# Jawbone_v2.net
KiCad netlist of a schematic drawn in EasyEDA Pro
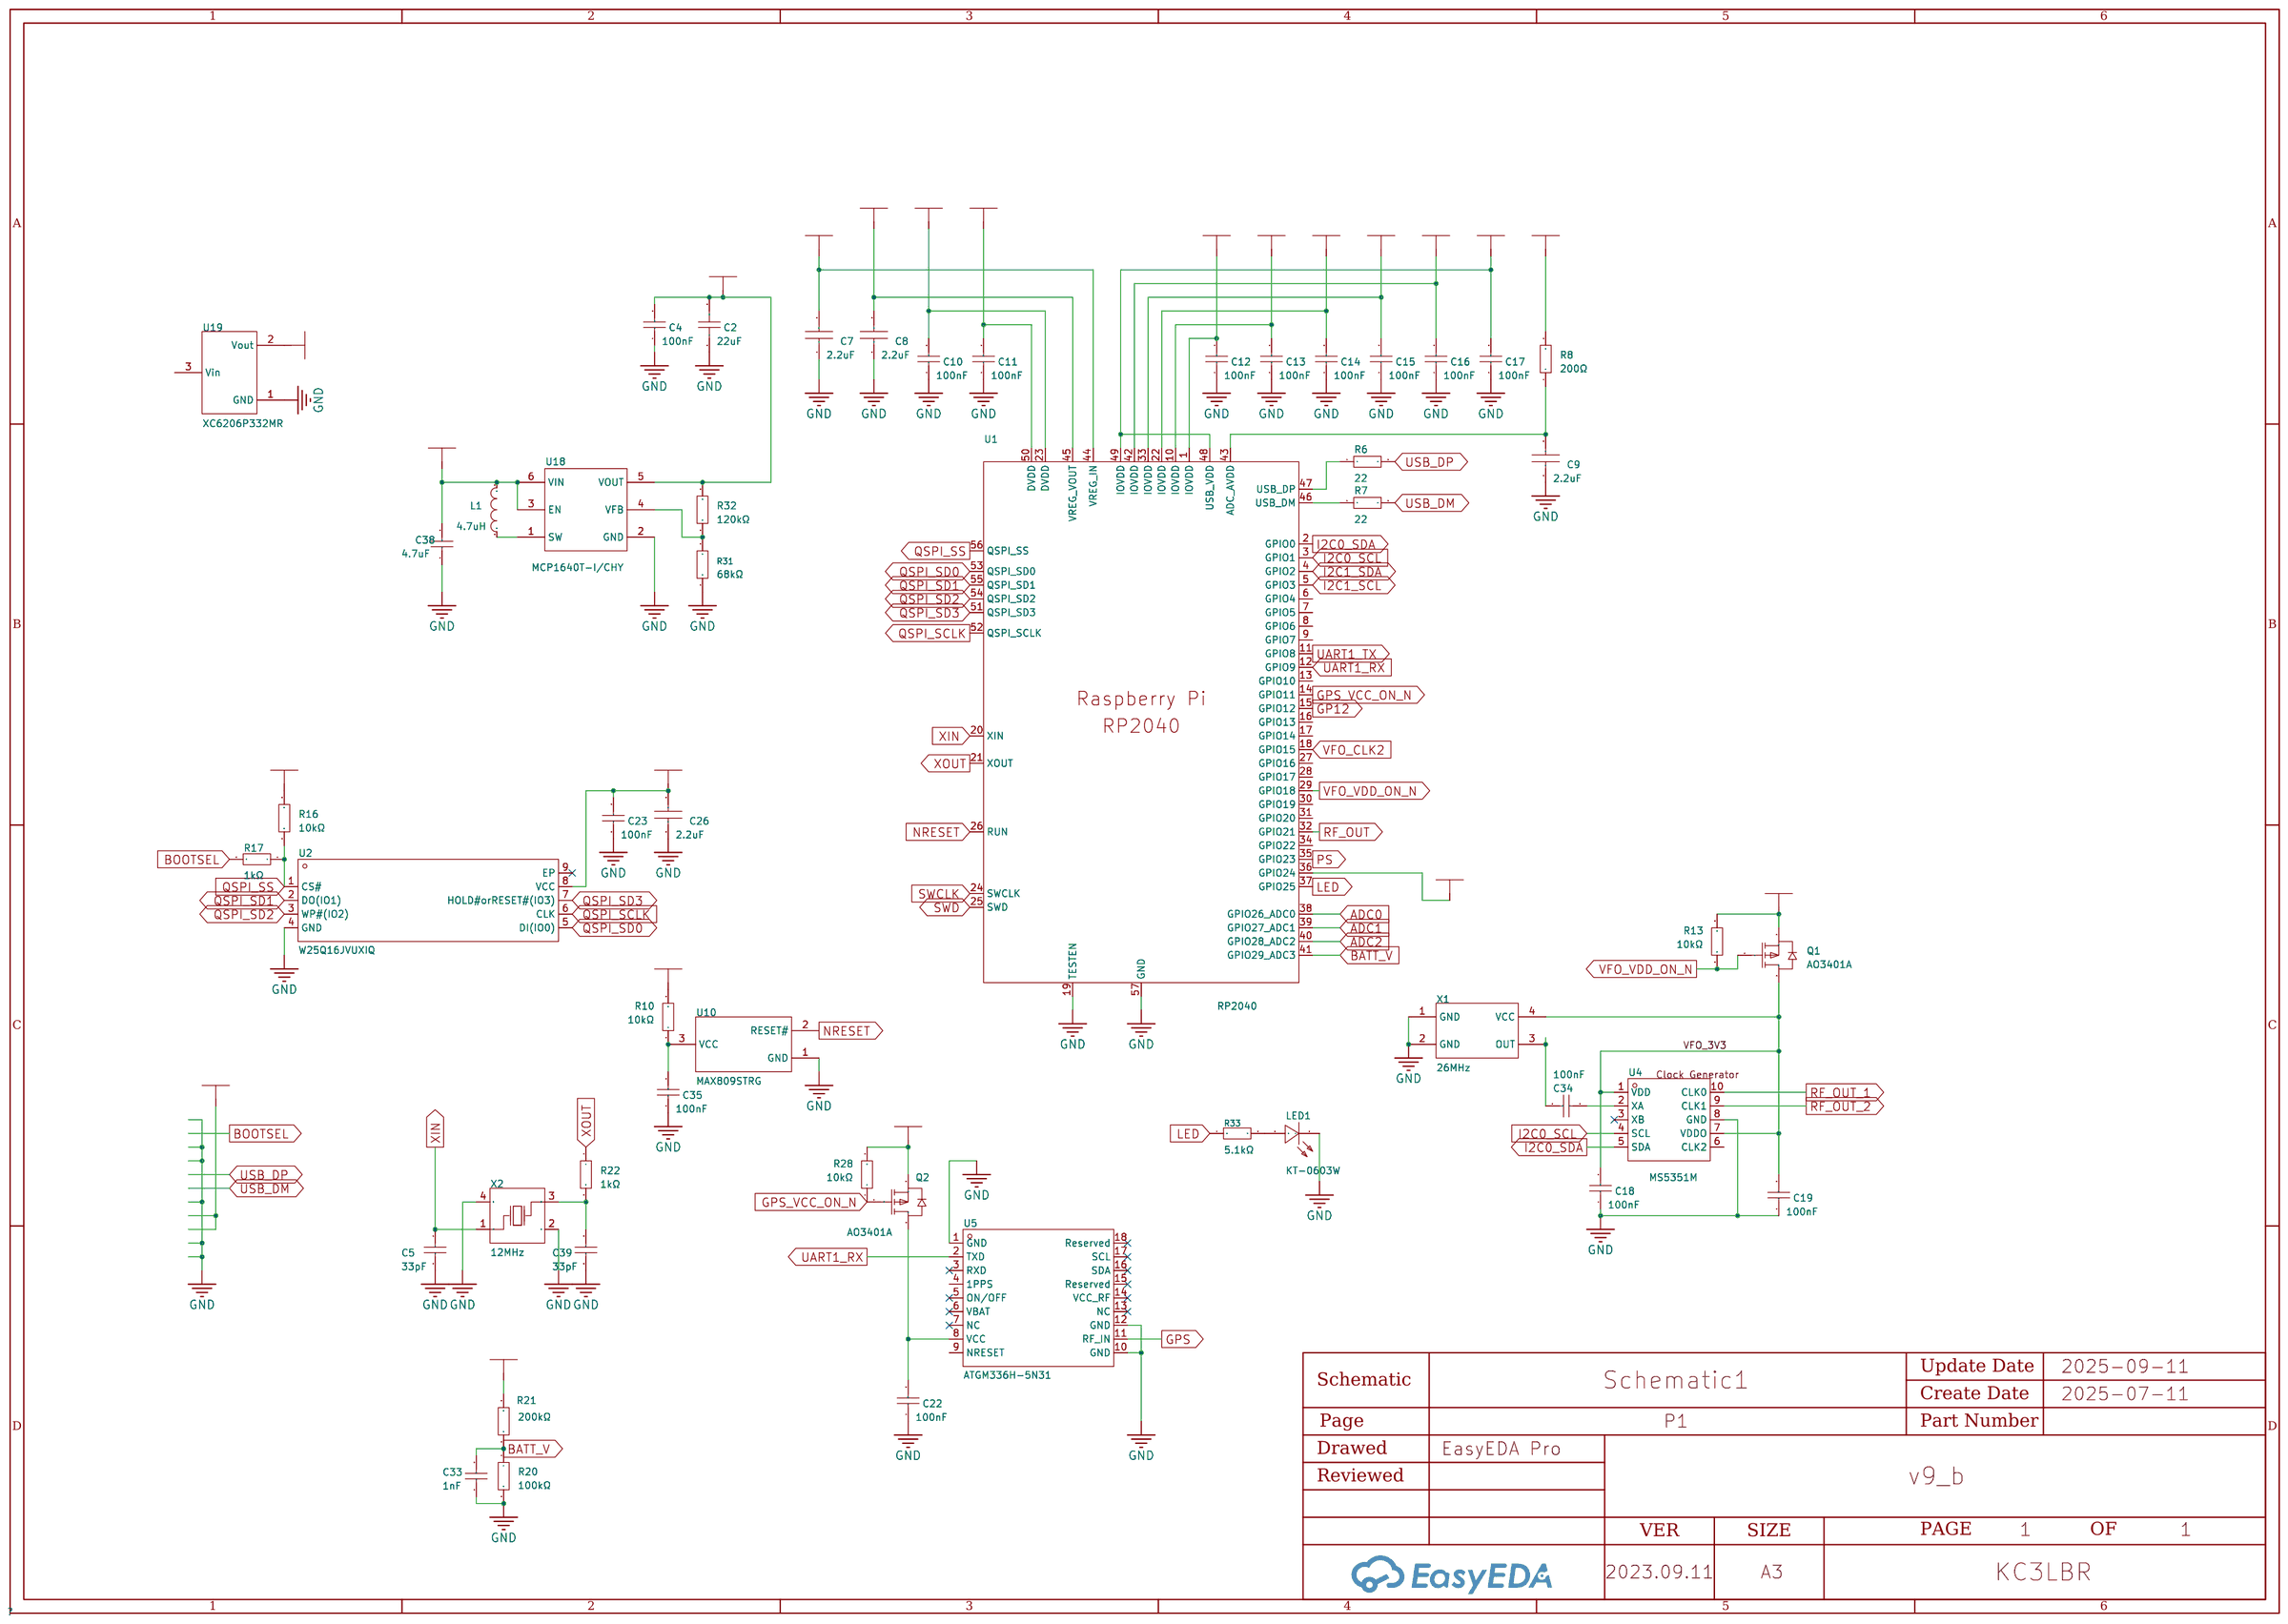
[diagram p0: schematic sheet]

(export (version "E")
  (design (tool "Eeschema 10.0.6"))
  (components
    (comp (ref "C2")
      (value "22uF")
      (footprint "easyedapro:C0603")
      (fields
        (field (name "Manufacturer Part") "CL10A226MQ8NRNC")
        (field (name "Manufacturer") "SAMSUNG(三星)")
      )
      (libsource (lib "easyedapro") (part "CL10A226MQ8NRNC"))
    )
    (comp (ref "C4")
      (value "100nF")
      (footprint "easyedapro:C0402_NEW")
      (fields
        (field (name "Manufacturer Part") "CL05B104KO5NNNC")
        (field (name "Manufacturer") "SAMSUNG(三星)")
      )
      (libsource (lib "easyedapro") (part "CL05B104KO5NNNC"))
    )
    (comp (ref "C5")
      (value "33pF")
      (footprint "easyedapro:C0402")
      (fields (field (name "Manufacturer Part") "0402CG330J500NT") (field (name "Manufacturer") "FH(风华)"))
      (libsource (lib "easyedapro") (part "0402CG330J500NT"))
    )
    (comp (ref "C7")
      (value "2.2uF")
      (footprint "easyedapro:C0402")
      (fields
        (field (name "Manufacturer Part") "CL05A225MQ5NSNC")
        (field (name "Manufacturer") "SAMSUNG(三星)")
      )
      (libsource (lib "easyedapro") (part "CL05A225MQ5NSNC"))
    )
    (comp (ref "C8")
      (value "2.2uF")
      (footprint "easyedapro:C0402")
      (fields
        (field (name "Manufacturer Part") "CL05A225MQ5NSNC")
        (field (name "Manufacturer") "SAMSUNG(三星)")
      )
      (libsource (lib "easyedapro") (part "CL05A225MQ5NSNC"))
    )
    (comp (ref "C9")
      (value "2.2uF")
      (footprint "easyedapro:C0402")
      (fields
        (field (name "Manufacturer Part") "CL05A225MQ5NSNC")
        (field (name "Manufacturer") "SAMSUNG(三星)")
      )
      (libsource (lib "easyedapro") (part "CL05A225MQ5NSNC"))
    )
    (comp (ref "C10")
      (value "100nF")
      (footprint "easyedapro:C0402_NEW")
      (fields
        (field (name "Manufacturer Part") "CL05B104KO5NNNC")
        (field (name "Manufacturer") "SAMSUNG(三星)")
      )
      (libsource (lib "easyedapro") (part "CL05B104KO5NNNC"))
    )
    (comp (ref "C11")
      (value "100nF")
      (footprint "easyedapro:C0402_NEW")
      (fields
        (field (name "Manufacturer Part") "CL05B104KO5NNNC")
        (field (name "Manufacturer") "SAMSUNG(三星)")
      )
      (libsource (lib "easyedapro") (part "CL05B104KO5NNNC"))
    )
    (comp (ref "C12")
      (value "100nF")
      (footprint "easyedapro:C0402_NEW")
      (fields
        (field (name "Manufacturer Part") "CL05B104KO5NNNC")
        (field (name "Manufacturer") "SAMSUNG(三星)")
      )
      (libsource (lib "easyedapro") (part "CL05B104KO5NNNC"))
    )
    (comp (ref "C13")
      (value "100nF")
      (footprint "easyedapro:C0402_NEW")
      (fields
        (field (name "Manufacturer Part") "CL05B104KO5NNNC")
        (field (name "Manufacturer") "SAMSUNG(三星)")
      )
      (libsource (lib "easyedapro") (part "CL05B104KO5NNNC"))
    )
    (comp (ref "C14")
      (value "100nF")
      (footprint "easyedapro:C0402_NEW")
      (fields
        (field (name "Manufacturer Part") "CL05B104KO5NNNC")
        (field (name "Manufacturer") "SAMSUNG(三星)")
      )
      (libsource (lib "easyedapro") (part "CL05B104KO5NNNC"))
    )
    (comp (ref "C15")
      (value "100nF")
      (footprint "easyedapro:C0402_NEW")
      (fields
        (field (name "Manufacturer Part") "CL05B104KO5NNNC")
        (field (name "Manufacturer") "SAMSUNG(三星)")
      )
      (libsource (lib "easyedapro") (part "CL05B104KO5NNNC"))
    )
    (comp (ref "C16")
      (value "100nF")
      (footprint "easyedapro:C0402_NEW")
      (fields
        (field (name "Manufacturer Part") "CL05B104KO5NNNC")
        (field (name "Manufacturer") "SAMSUNG(三星)")
      )
      (libsource (lib "easyedapro") (part "CL05B104KO5NNNC"))
    )
    (comp (ref "C17")
      (value "100nF")
      (footprint "easyedapro:C0402_NEW")
      (fields
        (field (name "Manufacturer Part") "CL05B104KO5NNNC")
        (field (name "Manufacturer") "SAMSUNG(三星)")
      )
      (libsource (lib "easyedapro") (part "CL05B104KO5NNNC"))
    )
    (comp (ref "C18")
      (value "100nF")
      (footprint "easyedapro:C0402_NEW")
      (fields
        (field (name "Manufacturer Part") "CL05B104KO5NNNC")
        (field (name "Manufacturer") "SAMSUNG(三星)")
      )
      (libsource (lib "easyedapro") (part "CL05B104KO5NNNC"))
    )
    (comp (ref "C19")
      (value "100nF")
      (footprint "easyedapro:C0402_NEW")
      (fields
        (field (name "Manufacturer Part") "CL05B104KO5NNNC")
        (field (name "Manufacturer") "SAMSUNG(三星)")
      )
      (libsource (lib "easyedapro") (part "CL05B104KO5NNNC"))
    )
    (comp (ref "C22")
      (value "100nF")
      (footprint "easyedapro:C0402_NEW")
      (fields
        (field (name "Manufacturer Part") "CL05B104KO5NNNC")
        (field (name "Manufacturer") "SAMSUNG(三星)")
      )
      (libsource (lib "easyedapro") (part "CL05B104KO5NNNC"))
    )
    (comp (ref "C23")
      (value "100nF")
      (footprint "easyedapro:C0402_NEW")
      (fields
        (field (name "Manufacturer Part") "CL05B104KO5NNNC")
        (field (name "Manufacturer") "SAMSUNG(三星)")
      )
      (libsource (lib "easyedapro") (part "CL05B104KO5NNNC"))
    )
    (comp (ref "C26")
      (value "2.2uF")
      (footprint "easyedapro:C0402")
      (fields
        (field (name "Manufacturer Part") "CL05A225MQ5NSNC")
        (field (name "Manufacturer") "SAMSUNG(三星)")
      )
      (libsource (lib "easyedapro") (part "CL05A225MQ5NSNC"))
    )
    (comp (ref "C33")
      (value "1nF")
      (footprint "easyedapro:C0402")
      (fields (field (name "Manufacturer Part") "0402B102K500NT") (field (name "Manufacturer") "FH(风华)"))
      (libsource (lib "easyedapro") (part "0402B102K500NT"))
    )
    (comp (ref "C34")
      (value "100nF")
      (footprint "easyedapro:C0402_NEW")
      (fields
        (field (name "Manufacturer Part") "CL05B104KO5NNNC")
        (field (name "Manufacturer") "SAMSUNG(三星)")
      )
      (libsource (lib "easyedapro") (part "CL05B104KO5NNNC"))
    )
    (comp (ref "C35")
      (value "100nF")
      (footprint "easyedapro:C0402_NEW")
      (fields
        (field (name "Manufacturer Part") "CL05B104KO5NNNC")
        (field (name "Manufacturer") "SAMSUNG(三星)")
      )
      (libsource (lib "easyedapro") (part "CL05B104KO5NNNC"))
    )
    (comp (ref "C38")
      (value "4.7uF")
      (footprint "easyedapro:C0603")
      (fields
        (field (name "Manufacturer Part") "CL10A475KO8NNNC")
        (field (name "Manufacturer") "SAMSUNG(三星)")
      )
      (libsource (lib "easyedapro") (part "CL10A475KO8NNNC"))
    )
    (comp (ref "C39")
      (value "33pF")
      (footprint "easyedapro:C0402")
      (fields (field (name "Manufacturer Part") "0402CG330J500NT") (field (name "Manufacturer") "FH(风华)"))
      (libsource (lib "easyedapro") (part "0402CG330J500NT"))
    )
    (comp (ref "L1")
      (value "4.7uH")
      (footprint "easyedapro:IND-SMD_L2.5-W1.8")
      (fields
        (field (name "Manufacturer Part") "CBC2518T4R7M")
        (field (name "Manufacturer") "TAIYO YUDEN(太诱)")
      )
      (libsource (lib "easyedapro") (part "CBC2518T4R7M"))
    )
    (comp (ref "LED1")
      (value "KT-0603W")
      (footprint "easyedapro:LED0603-R-RD_WHITE")
      (fields (field (name "Manufacturer") "KENTO"))
      (libsource (lib "easyedapro") (part "0603White light_C2290"))
    )
    (comp (ref "Q1")
      (value "AO3401A")
      (footprint "easyedapro:SOT-23_L2.9-W1.3-P1.90-LS2.4-BR")
      (fields (field (name "Manufacturer") "AOS"))
      (libsource (lib "easyedapro") (part "AO3401A"))
    )
    (comp (ref "Q2")
      (value "AO3401A")
      (footprint "easyedapro:SOT-23_L2.9-W1.3-P1.90-LS2.4-BR")
      (fields (field (name "Manufacturer") "AOS"))
      (libsource (lib "easyedapro") (part "AO3401A"))
    )
    (comp (ref "R6")
      (value "22")
      (footprint "easyedapro:R0402")
      (fields
        (field (name "Manufacturer Part") "0402WGF220JTCE")
        (field (name "Manufacturer") "UNI-ROYAL(厚声)")
      )
      (libsource (lib "easyedapro") (part "0402WGF220JTCE"))
    )
    (comp (ref "R7")
      (value "22")
      (footprint "easyedapro:R0402")
      (fields
        (field (name "Manufacturer Part") "0402WGF220JTCE")
        (field (name "Manufacturer") "UNI-ROYAL(厚声)")
      )
      (libsource (lib "easyedapro") (part "0402WGF220JTCE"))
    )
    (comp (ref "R8")
      (value "200Ω")
      (footprint "easyedapro:R0402")
      (fields
        (field (name "Manufacturer Part") "0402WGF2000TCE")
        (field (name "Manufacturer") "UNI-ROYAL(厚声)")
      )
      (libsource (lib "easyedapro") (part "0402WGF2000TCE"))
    )
    (comp (ref "R10")
      (value "10kΩ")
      (footprint "easyedapro:R0402")
      (fields
        (field (name "Manufacturer Part") "0402WGF1002TCE")
        (field (name "Manufacturer") "UNI-ROYAL(厚声)")
      )
      (libsource (lib "easyedapro") (part "0402WGF1002TCE"))
    )
    (comp (ref "R13")
      (value "10kΩ")
      (footprint "easyedapro:R0402")
      (fields
        (field (name "Manufacturer Part") "0402WGF1002TCE")
        (field (name "Manufacturer") "UNI-ROYAL(厚声)")
      )
      (libsource (lib "easyedapro") (part "0402WGF1002TCE"))
    )
    (comp (ref "R16")
      (value "10kΩ")
      (footprint "easyedapro:R0402")
      (fields
        (field (name "Manufacturer Part") "0402WGF1002TCE")
        (field (name "Manufacturer") "UNI-ROYAL(厚声)")
      )
      (libsource (lib "easyedapro") (part "0402WGF1002TCE"))
    )
    (comp (ref "R17")
      (value "1kΩ")
      (footprint "easyedapro:R0402")
      (fields
        (field (name "Manufacturer Part") "0402WGF1001TCE")
        (field (name "Manufacturer") "UNI-ROYAL(厚声)")
      )
      (libsource (lib "easyedapro") (part "0402WGF1001TCE"))
    )
    (comp (ref "R20")
      (value "100kΩ")
      (footprint "easyedapro:R0402")
      (fields
        (field (name "Manufacturer Part") "0402WGF1003TCE")
        (field (name "Manufacturer") "UNI-ROYAL(厚声)")
      )
      (libsource (lib "easyedapro") (part "0402WGF1003TCE"))
    )
    (comp (ref "R21")
      (value "200kΩ")
      (footprint "easyedapro:R0402")
      (fields
        (field (name "Manufacturer Part") "0402WGF2003TCE")
        (field (name "Manufacturer") "UNI-ROYAL(厚声)")
      )
      (libsource (lib "easyedapro") (part "0402WGF2003TCE"))
    )
    (comp (ref "R22")
      (value "1kΩ")
      (footprint "easyedapro:R0402")
      (fields
        (field (name "Manufacturer Part") "0402WGF1001TCE")
        (field (name "Manufacturer") "UNI-ROYAL(厚声)")
      )
      (libsource (lib "easyedapro") (part "0402WGF1001TCE"))
    )
    (comp (ref "R28")
      (value "10kΩ")
      (footprint "easyedapro:R0402")
      (fields
        (field (name "Manufacturer Part") "0402WGF1002TCE")
        (field (name "Manufacturer") "UNI-ROYAL(厚声)")
      )
      (libsource (lib "easyedapro") (part "0402WGF1002TCE"))
    )
    (comp (ref "R31")
      (value "68kΩ")
      (footprint "easyedapro:R0603")
      (fields
        (field (name "Manufacturer Part") "0603WAF6802T5E")
        (field (name "Manufacturer") "UNI-ROYAL(厚声)")
      )
      (libsource (lib "easyedapro") (part "0603WAF6802T5E"))
    )
    (comp (ref "R32")
      (value "120kΩ")
      (footprint "easyedapro:R0603")
      (fields
        (field (name "Manufacturer Part") "0603WAF1203T5E")
        (field (name "Manufacturer") "UNI-ROYAL(厚声)")
      )
      (libsource (lib "easyedapro") (part "0603WAF1203T5E"))
    )
    (comp (ref "R33")
      (value "5.1kΩ")
      (footprint "easyedapro:R0402")
      (fields
        (field (name "Manufacturer Part") "0402WGF5101TCE")
        (field (name "Manufacturer") "UNI-ROYAL(厚声)")
      )
      (libsource (lib "easyedapro") (part "0402WGF5101TCE"))
    )
    (comp (ref "U1")
      (value "RP2040")
      (footprint "easyedapro:LQFN-56_L7.0-W7.0-P0.4-EP")
      (fields (field (name "Manufacturer") "Raspberry Pi(树莓派)"))
      (libsource (lib "easyedapro") (part "RP2040"))
    )
    (comp (ref "U2")
      (value "W25Q16JVUXIQ")
      (footprint "easyedapro:USON-8_L3.0-W2.0-P0.50-BL-EP")
      (fields (field (name "Manufacturer") "WINBOND(华邦)"))
      (libsource (lib "easyedapro") (part "W25Q16JVUXIQ"))
    )
    (comp (ref "U4")
      (value "MS5351M")
      (footprint "easyedapro:MSOP-10_L3.0-W3.0-P0.50-LS5.0-BL")
      (description "Clock Generator")
      (fields (field (name "Manufacturer") "杭州瑞盟"))
      (libsource (lib "easyedapro") (part "MS5351M"))
    )
    (comp (ref "U5")
      (value "ATGM336H-5N31")
      (footprint "easyedapro:GPSM-SMD_ATGM336H-TR")
      (fields (field (name "Manufacturer") "杭州中科微"))
      (libsource (lib "easyedapro") (part "ATGM336H-5N31"))
    )
    (comp (ref "U10")
      (value "MAX809STRG")
      (footprint "easyedapro:SOT-23-3_L2.9-W1.6-P1.90-LS2.8-BR")
      (fields (field (name "Manufacturer") "onsemi(安森美)"))
      (libsource (lib "easyedapro") (part "MAX809STRG"))
    )
    (comp (ref "U18")
      (value "MCP1640T-I/CHY")
      (footprint "easyedapro:SOT-23-6_L2.9-W1.6-P0.95-LS2.8-BR")
      (fields (field (name "Manufacturer") "MICROCHIP(美国微芯)"))
      (libsource (lib "easyedapro") (part "MCP1640T-I/CHY"))
    )
    (comp (ref "U19")
      (value "XC6206P332MR")
      (footprint "easyedapro:SOT-23-3_L2.9-W1.6-P1.90-LS2.8-BR")
      (fields (field (name "Manufacturer") "TOREX(特瑞仕)"))
      (libsource (lib "easyedapro") (part "XC6206P332MR"))
    )
    (comp (ref "X1")
      (value "26MHz")
      (footprint "easyedapro:OSC-SMD_4P-L2.5-W2.0-BL")
      (fields (field (name "Manufacturer Part") "1XXB26000MAA") (field (name "Manufacturer") "KDS(大真空)"))
      (libsource (lib "easyedapro") (part "1XXB26000MAA"))
    )
    (comp (ref "X2")
      (value "12MHz")
      (footprint "easyedapro:OSC-SMD_4P-L3.2-W2.5-BL")
      (fields (field (name "Manufacturer Part") "X322512MSB4SI") (field (name "Manufacturer") "YXC(扬兴晶振)"))
      (libsource (lib "easyedapro") (part "X322512MSB4SI"))
    )
  )
  (nets
    (net (code "1") (name "/VFO_3V3") (class "Default")
      (node (ref "C18") (pin "2") (pinfunction "2_2") (pintype "input"))
      (node (ref "C19") (pin "2") (pinfunction "2_2") (pintype "input"))
      (node (ref "Q1") (pin "3") (pinfunction "D_3") (pintype "input"))
      (node (ref "U4") (pin "1") (pinfunction "VDD_1") (pintype "input"))
      (node (ref "U4") (pin "7") (pinfunction "VDDO_7") (pintype "input"))
      (node (ref "X1") (pin "4") (pinfunction "VCC_4") (pintype "input"))
    )
    (net (code "2") (name "1V1") (class "Default")
      (node (ref "C10") (pin "2") (pinfunction "2_2") (pintype "input"))
      (node (ref "C11") (pin "2") (pinfunction "2_2") (pintype "input"))
      (node (ref "C8") (pin "2") (pinfunction "2_2") (pintype "input"))
      (node (ref "U1") (pin "23") (pinfunction "DVDD_23") (pintype "bidirectional"))
      (node (ref "U1") (pin "45") (pinfunction "VREG_VOUT_45") (pintype "bidirectional"))
      (node (ref "U1") (pin "50") (pinfunction "DVDD_50") (pintype "bidirectional"))
    )
    (net (code "3") (name "3V3") (class "Default")
      (node (ref "C12") (pin "2") (pinfunction "2_2") (pintype "input"))
      (node (ref "C13") (pin "2") (pinfunction "2_2") (pintype "input"))
      (node (ref "C14") (pin "2") (pinfunction "2_2") (pintype "input"))
      (node (ref "C15") (pin "2") (pinfunction "2_2") (pintype "input"))
      (node (ref "C16") (pin "2") (pinfunction "2_2") (pintype "input"))
      (node (ref "C17") (pin "2") (pinfunction "2_2") (pintype "input"))
      (node (ref "C2") (pin "2") (pinfunction "2_2") (pintype "input"))
      (node (ref "C23") (pin "2") (pinfunction "2_2") (pintype "input"))
      (node (ref "C26") (pin "2") (pinfunction "2_2") (pintype "input"))
      (node (ref "C4") (pin "2") (pinfunction "2_2") (pintype "input"))
      (node (ref "C7") (pin "2") (pinfunction "2_2") (pintype "input"))
      (node (ref "Q1") (pin "2") (pinfunction "S_2") (pintype "input"))
      (node (ref "Q2") (pin "2") (pinfunction "S_2") (pintype "input"))
      (node (ref "R10") (pin "2") (pinfunction "2_2") (pintype "input"))
      (node (ref "R13") (pin "2") (pinfunction "2_2") (pintype "input"))
      (node (ref "R16") (pin "2") (pinfunction "2_2") (pintype "input"))
      (node (ref "R28") (pin "2") (pinfunction "2_2") (pintype "input"))
      (node (ref "R32") (pin "2") (pinfunction "2_2") (pintype "input"))
      (node (ref "R8") (pin "2") (pinfunction "2_2") (pintype "input"))
      (node (ref "U1") (pin "1") (pinfunction "IOVDD_1") (pintype "bidirectional"))
      (node (ref "U1") (pin "10") (pinfunction "IOVDD_10") (pintype "bidirectional"))
      (node (ref "U1") (pin "22") (pinfunction "IOVDD_22") (pintype "bidirectional"))
      (node (ref "U1") (pin "33") (pinfunction "IOVDD_33") (pintype "bidirectional"))
      (node (ref "U1") (pin "36") (pinfunction "GPIO24_36") (pintype "bidirectional"))
      (node (ref "U1") (pin "42") (pinfunction "IOVDD_42") (pintype "bidirectional"))
      (node (ref "U1") (pin "44") (pinfunction "VREG_IN_44") (pintype "bidirectional"))
      (node (ref "U1") (pin "48") (pinfunction "USB_VDD_48") (pintype "bidirectional"))
      (node (ref "U1") (pin "49") (pinfunction "IOVDD_49") (pintype "bidirectional"))
      (node (ref "U18") (pin "5") (pinfunction "VOUT_5") (pintype "input"))
      (node (ref "U2") (pin "8") (pinfunction "VCC_8") (pintype "input"))
    )
    (net (code "4") (name "ADC0") (class "Default")
      (node (ref "U1") (pin "38") (pinfunction "GPIO26_ADC0_38") (pintype "bidirectional"))
    )
    (net (code "5") (name "ADC1") (class "Default")
      (node (ref "U1") (pin "39") (pinfunction "GPIO27_ADC1_39") (pintype "bidirectional"))
    )
    (net (code "6") (name "ADC2") (class "Default")
      (node (ref "U1") (pin "40") (pinfunction "GPIO28_ADC2_40") (pintype "bidirectional"))
    )
    (net (code "7") (name "BATT_V") (class "Default")
      (node (ref "C33") (pin "2") (pinfunction "2_2") (pintype "input"))
      (node (ref "R20") (pin "1") (pinfunction "1_1") (pintype "input"))
      (node (ref "R21") (pin "1") (pinfunction "1_1") (pintype "input"))
      (node (ref "U1") (pin "41") (pinfunction "GPIO29_ADC3_41") (pintype "bidirectional"))
    )
    (net (code "8") (name "BOOTSEL") (class "Default")
      (node (ref "R17") (pin "2") (pinfunction "2_2") (pintype "input"))
    )
    (net (code "9") (name "GND") (class "Default")
      (node (ref "C10") (pin "1") (pinfunction "1_1") (pintype "input"))
      (node (ref "C11") (pin "1") (pinfunction "1_1") (pintype "input"))
      (node (ref "C12") (pin "1") (pinfunction "1_1") (pintype "input"))
      (node (ref "C13") (pin "1") (pinfunction "1_1") (pintype "input"))
      (node (ref "C14") (pin "1") (pinfunction "1_1") (pintype "input"))
      (node (ref "C15") (pin "1") (pinfunction "1_1") (pintype "input"))
      (node (ref "C16") (pin "1") (pinfunction "1_1") (pintype "input"))
      (node (ref "C17") (pin "1") (pinfunction "1_1") (pintype "input"))
      (node (ref "C18") (pin "1") (pinfunction "1_1") (pintype "input"))
      (node (ref "C19") (pin "1") (pinfunction "1_1") (pintype "input"))
      (node (ref "C2") (pin "1") (pinfunction "1_1") (pintype "input"))
      (node (ref "C22") (pin "1") (pinfunction "1_1") (pintype "input"))
      (node (ref "C23") (pin "1") (pinfunction "1_1") (pintype "input"))
      (node (ref "C26") (pin "1") (pinfunction "1_1") (pintype "input"))
      (node (ref "C33") (pin "1") (pinfunction "1_1") (pintype "input"))
      (node (ref "C35") (pin "1") (pinfunction "1_1") (pintype "input"))
      (node (ref "C38") (pin "1") (pinfunction "1_1") (pintype "input"))
      (node (ref "C39") (pin "1") (pinfunction "1_1") (pintype "input"))
      (node (ref "C4") (pin "1") (pinfunction "1_1") (pintype "input"))
      (node (ref "C5") (pin "1") (pinfunction "1_1") (pintype "input"))
      (node (ref "C7") (pin "1") (pinfunction "1_1") (pintype "input"))
      (node (ref "C8") (pin "1") (pinfunction "1_1") (pintype "input"))
      (node (ref "C9") (pin "1") (pinfunction "1_1") (pintype "input"))
      (node (ref "LED1") (pin "2") (pinfunction "K_2") (pintype "unspecified"))
      (node (ref "R20") (pin "2") (pinfunction "2_2") (pintype "input"))
      (node (ref "R31") (pin "1") (pinfunction "1_1") (pintype "input"))
      (node (ref "U1") (pin "19") (pinfunction "TESTEN_19") (pintype "input"))
      (node (ref "U1") (pin "57") (pinfunction "GND_57") (pintype "bidirectional"))
      (node (ref "U10") (pin "1") (pinfunction "GND_1") (pintype "input"))
      (node (ref "U18") (pin "2") (pinfunction "GND_2") (pintype "input"))
      (node (ref "U19") (pin "1") (pinfunction "GND_1") (pintype "unspecified"))
      (node (ref "U2") (pin "4") (pinfunction "GND_4") (pintype "input"))
      (node (ref "U4") (pin "8") (pinfunction "GND_8") (pintype "input"))
      (node (ref "U5") (pin "1") (pinfunction "GND_1") (pintype "input"))
      (node (ref "U5") (pin "10") (pinfunction "GND_10") (pintype "input"))
      (node (ref "U5") (pin "12") (pinfunction "GND_12") (pintype "input"))
      (node (ref "X1") (pin "1") (pinfunction "GND_1") (pintype "input"))
      (node (ref "X1") (pin "2") (pinfunction "GND_2") (pintype "input"))
      (node (ref "X2") (pin "2") (pinfunction "GND_2") (pintype "input"))
      (node (ref "X2") (pin "4") (pinfunction "GND_4") (pintype "input"))
    )
    (net (code "10") (name "GP12") (class "Default")
      (node (ref "U1") (pin "15") (pinfunction "GPIO12_15") (pintype "bidirectional"))
    )
    (net (code "11") (name "GPS") (class "Default")
      (node (ref "U5") (pin "11") (pinfunction "RF_IN_11") (pintype "input"))
    )
    (net (code "12") (name "GPS_VCC_ON_N") (class "Default")
      (node (ref "Q2") (pin "1") (pinfunction "G_1") (pintype "input"))
      (node (ref "R28") (pin "1") (pinfunction "1_1") (pintype "input"))
      (node (ref "U1") (pin "14") (pinfunction "GPIO11_14") (pintype "bidirectional"))
    )
    (net (code "13") (name "I2C0_SCL") (class "Default")
      (node (ref "U1") (pin "3") (pinfunction "GPIO1_3") (pintype "bidirectional"))
      (node (ref "U4") (pin "4") (pinfunction "SCL_4") (pintype "input"))
    )
    (net (code "14") (name "I2C0_SDA") (class "Default")
      (node (ref "U1") (pin "2") (pinfunction "GPIO0_2") (pintype "bidirectional"))
      (node (ref "U4") (pin "5") (pinfunction "SDA_5") (pintype "input"))
    )
    (net (code "15") (name "I2C1_SCL") (class "Default")
      (node (ref "U1") (pin "5") (pinfunction "GPIO3_5") (pintype "bidirectional"))
    )
    (net (code "16") (name "I2C1_SDA") (class "Default")
      (node (ref "U1") (pin "4") (pinfunction "GPIO2_4") (pintype "bidirectional"))
    )
    (net (code "17") (name "LED") (class "Default")
      (node (ref "R33") (pin "1") (pinfunction "1_1") (pintype "input"))
      (node (ref "U1") (pin "37") (pinfunction "GPIO25_37") (pintype "bidirectional"))
    )
    (net (code "18") (name "NRESET") (class "Default")
      (node (ref "U1") (pin "26") (pinfunction "RUN_26") (pintype "input"))
      (node (ref "U10") (pin "2") (pinfunction "RESET#_2") (pintype "input"))
    )
    (net (code "19") (name "Net-(LED1-A)") (class "Default")
      (node (ref "LED1") (pin "1") (pinfunction "A_1") (pintype "unspecified"))
      (node (ref "R33") (pin "2") (pinfunction "2_2") (pintype "input"))
    )
    (net (code "20") (name "Net-(Q2-D)") (class "Default")
      (node (ref "C22") (pin "2") (pinfunction "2_2") (pintype "input"))
      (node (ref "Q2") (pin "3") (pinfunction "D_3") (pintype "input"))
      (node (ref "U5") (pin "8") (pinfunction "VCC_8") (pintype "input"))
    )
    (net (code "21") (name "Net-(U1-ADC_AVDD)") (class "Default")
      (node (ref "C9") (pin "2") (pinfunction "2_2") (pintype "input"))
      (node (ref "R8") (pin "1") (pinfunction "1_1") (pintype "input"))
      (node (ref "U1") (pin "43") (pinfunction "ADC_AVDD_43") (pintype "bidirectional"))
    )
    (net (code "22") (name "Net-(U1-USB_DM)") (class "Default")
      (node (ref "R7") (pin "1") (pinfunction "1_1") (pintype "input"))
      (node (ref "U1") (pin "46") (pinfunction "USB_DM_46") (pintype "bidirectional"))
    )
    (net (code "23") (name "Net-(U1-USB_DP)") (class "Default")
      (node (ref "R6") (pin "1") (pinfunction "1_1") (pintype "input"))
      (node (ref "U1") (pin "47") (pinfunction "USB_DP_47") (pintype "bidirectional"))
    )
    (net (code "24") (name "Net-(U4-XA)") (class "Default")
      (node (ref "C34") (pin "1") (pinfunction "1_1") (pintype "input"))
      (node (ref "U4") (pin "2") (pinfunction "XA_2") (pintype "input"))
    )
    (net (code "25") (name "Net-(U10-VCC)") (class "Default")
      (node (ref "C35") (pin "2") (pinfunction "2_2") (pintype "input"))
      (node (ref "R10") (pin "1") (pinfunction "1_1") (pintype "input"))
      (node (ref "U10") (pin "3") (pinfunction "VCC_3") (pintype "input"))
    )
    (net (code "26") (name "Net-(U18-SW)") (class "Default")
      (node (ref "L1") (pin "1") (pinfunction "1_1") (pintype "input"))
      (node (ref "U18") (pin "1") (pinfunction "SW_1") (pintype "input"))
    )
    (net (code "27") (name "Net-(U18-VFB)") (class "Default")
      (node (ref "R31") (pin "2") (pinfunction "2_2") (pintype "input"))
      (node (ref "R32") (pin "1") (pinfunction "1_1") (pintype "input"))
      (node (ref "U18") (pin "4") (pinfunction "VFB_4") (pintype "input"))
    )
    (net (code "28") (name "Net-(X1-OUT)") (class "Default")
      (node (ref "C34") (pin "2") (pinfunction "2_2") (pintype "input"))
      (node (ref "X1") (pin "3") (pinfunction "OUT_3") (pintype "input"))
    )
    (net (code "29") (name "Net-(X2-OSC2)") (class "Default")
      (node (ref "C39") (pin "2") (pinfunction "2_2") (pintype "input"))
      (node (ref "R22") (pin "2") (pinfunction "2_2") (pintype "input"))
      (node (ref "X2") (pin "3") (pinfunction "OSC2_3") (pintype "input"))
    )
    (net (code "30") (name "PS") (class "Default")
      (node (ref "U1") (pin "35") (pinfunction "GPIO23_35") (pintype "bidirectional"))
    )
    (net (code "31") (name "QSPI_SCLK") (class "Default")
      (node (ref "U1") (pin "52") (pinfunction "QSPI_SCLK_52") (pintype "output"))
      (node (ref "U2") (pin "6") (pinfunction "CLK_6") (pintype "input"))
    )
    (net (code "32") (name "QSPI_SD0") (class "Default")
      (node (ref "U1") (pin "53") (pinfunction "QSPI_SD0_53") (pintype "bidirectional"))
      (node (ref "U2") (pin "5") (pinfunction "DI(IO0)_5") (pintype "input"))
    )
    (net (code "33") (name "QSPI_SD1") (class "Default")
      (node (ref "U1") (pin "55") (pinfunction "QSPI_SD1_55") (pintype "bidirectional"))
      (node (ref "U2") (pin "2") (pinfunction "DO(IO1)_2") (pintype "input"))
    )
    (net (code "34") (name "QSPI_SD2") (class "Default")
      (node (ref "U1") (pin "54") (pinfunction "QSPI_SD2_54") (pintype "bidirectional"))
      (node (ref "U2") (pin "3") (pinfunction "WP#(IO2)_3") (pintype "input"))
    )
    (net (code "35") (name "QSPI_SD3") (class "Default")
      (node (ref "U1") (pin "51") (pinfunction "QSPI_SD3_51") (pintype "bidirectional"))
      (node (ref "U2") (pin "7") (pinfunction "HOLD#orRESET#(IO3)_7") (pintype "input"))
    )
    (net (code "36") (name "QSPI_SS") (class "Default")
      (node (ref "R16") (pin "1") (pinfunction "1_1") (pintype "input"))
      (node (ref "R17") (pin "1") (pinfunction "1_1") (pintype "input"))
      (node (ref "U1") (pin "56") (pinfunction "QSPI_SS_56") (pintype "bidirectional"))
      (node (ref "U2") (pin "1") (pinfunction "CS#_1") (pintype "input"))
    )
    (net (code "37") (name "RF_OUT") (class "Default")
      (node (ref "U1") (pin "32") (pinfunction "GPIO21_32") (pintype "bidirectional"))
    )
    (net (code "38") (name "RF_OUT_1") (class "Default")
      (node (ref "U4") (pin "10") (pinfunction "CLK0_10") (pintype "input"))
    )
    (net (code "39") (name "RF_OUT_2") (class "Default")
      (node (ref "U4") (pin "9") (pinfunction "CLK1_9") (pintype "input"))
    )
    (net (code "40") (name "SWCLK") (class "Default")
      (node (ref "U1") (pin "24") (pinfunction "SWCLK_24") (pintype "output"))
    )
    (net (code "41") (name "SWD") (class "Default")
      (node (ref "U1") (pin "25") (pinfunction "SWD_25") (pintype "bidirectional"))
    )
    (net (code "42") (name "UART1_RX") (class "Default")
      (node (ref "U1") (pin "12") (pinfunction "GPIO9_12") (pintype "bidirectional"))
      (node (ref "U5") (pin "2") (pinfunction "TXD_2") (pintype "input"))
    )
    (net (code "43") (name "UART1_TX") (class "Default")
      (node (ref "U1") (pin "11") (pinfunction "GPIO8_11") (pintype "bidirectional"))
    )
    (net (code "44") (name "USB_DM") (class "Default")
      (node (ref "R7") (pin "2") (pinfunction "2_2") (pintype "input"))
    )
    (net (code "45") (name "USB_DP") (class "Default")
      (node (ref "R6") (pin "2") (pinfunction "2_2") (pintype "input"))
    )
    (net (code "46") (name "VBUS") (class "Default")
      (node (ref "C38") (pin "2") (pinfunction "2_2") (pintype "input"))
      (node (ref "L1") (pin "2") (pinfunction "2_2") (pintype "input"))
      (node (ref "R21") (pin "2") (pinfunction "2_2") (pintype "input"))
      (node (ref "U18") (pin "3") (pinfunction "EN_3") (pintype "input"))
      (node (ref "U18") (pin "6") (pinfunction "VIN_6") (pintype "input"))
      (node (ref "U19") (pin "2") (pinfunction "Vout_2") (pintype "unspecified"))
    )
    (net (code "47") (name "VFO_CLK2") (class "Default")
      (node (ref "U1") (pin "18") (pinfunction "GPIO15_18") (pintype "bidirectional"))
    )
    (net (code "48") (name "VFO_VDD_ON_N") (class "Default")
      (node (ref "Q1") (pin "1") (pinfunction "G_1") (pintype "input"))
      (node (ref "R13") (pin "1") (pinfunction "1_1") (pintype "input"))
      (node (ref "U1") (pin "29") (pinfunction "GPIO18_29") (pintype "bidirectional"))
    )
    (net (code "49") (name "XIN") (class "Default")
      (node (ref "C5") (pin "2") (pinfunction "2_2") (pintype "input"))
      (node (ref "U1") (pin "20") (pinfunction "XIN_20") (pintype "input"))
      (node (ref "X2") (pin "1") (pinfunction "OSC1_1") (pintype "input"))
    )
    (net (code "50") (name "XOUT") (class "Default")
      (node (ref "R22") (pin "1") (pinfunction "1_1") (pintype "input"))
      (node (ref "U1") (pin "21") (pinfunction "XOUT_21") (pintype "input"))
    )
    (net (code "51") (name "unconnected-(U1-GPIO4-Pad6)") (class "Default")
      (node (ref "U1") (pin "6") (pinfunction "GPIO4_6") (pintype "bidirectional"))
    )
    (net (code "52") (name "unconnected-(U1-GPIO5-Pad7)") (class "Default")
      (node (ref "U1") (pin "7") (pinfunction "GPIO5_7") (pintype "bidirectional"))
    )
    (net (code "53") (name "unconnected-(U1-GPIO6-Pad8)") (class "Default")
      (node (ref "U1") (pin "8") (pinfunction "GPIO6_8") (pintype "bidirectional"))
    )
    (net (code "54") (name "unconnected-(U1-GPIO7-Pad9)") (class "Default")
      (node (ref "U1") (pin "9") (pinfunction "GPIO7_9") (pintype "bidirectional"))
    )
    (net (code "55") (name "unconnected-(U1-GPIO10-Pad13)") (class "Default")
      (node (ref "U1") (pin "13") (pinfunction "GPIO10_13") (pintype "bidirectional"))
    )
    (net (code "56") (name "unconnected-(U1-GPIO13-Pad16)") (class "Default")
      (node (ref "U1") (pin "16") (pinfunction "GPIO13_16") (pintype "bidirectional"))
    )
    (net (code "57") (name "unconnected-(U1-GPIO14-Pad17)") (class "Default")
      (node (ref "U1") (pin "17") (pinfunction "GPIO14_17") (pintype "bidirectional"))
    )
    (net (code "58") (name "unconnected-(U1-GPIO16-Pad27)") (class "Default")
      (node (ref "U1") (pin "27") (pinfunction "GPIO16_27") (pintype "bidirectional"))
    )
    (net (code "59") (name "unconnected-(U1-GPIO17-Pad28)") (class "Default")
      (node (ref "U1") (pin "28") (pinfunction "GPIO17_28") (pintype "bidirectional"))
    )
    (net (code "60") (name "unconnected-(U1-GPIO19-Pad30)") (class "Default")
      (node (ref "U1") (pin "30") (pinfunction "GPIO19_30") (pintype "bidirectional"))
    )
    (net (code "61") (name "unconnected-(U1-GPIO20-Pad31)") (class "Default")
      (node (ref "U1") (pin "31") (pinfunction "GPIO20_31") (pintype "bidirectional"))
    )
    (net (code "62") (name "unconnected-(U1-GPIO22-Pad34)") (class "Default")
      (node (ref "U1") (pin "34") (pinfunction "GPIO22_34") (pintype "bidirectional"))
    )
    (net (code "63") (name "unconnected-(U2-EP-Pad9)") (class "Default")
      (node (ref "U2") (pin "9") (pinfunction "EP_9") (pintype "input+no_connect"))
    )
    (net (code "64") (name "unconnected-(U4-CLK2-Pad6)") (class "Default")
      (node (ref "U4") (pin "6") (pinfunction "CLK2_6") (pintype "input"))
    )
    (net (code "65") (name "unconnected-(U4-XB-Pad3)") (class "Default")
      (node (ref "U4") (pin "3") (pinfunction "XB_3") (pintype "input+no_connect"))
    )
    (net (code "66") (name "unconnected-(U5-1PPS-Pad4)") (class "Default")
      (node (ref "U5") (pin "4") (pinfunction "1PPS_4") (pintype "input"))
    )
    (net (code "67") (name "unconnected-(U5-NC-Pad7)") (class "Default")
      (node (ref "U5") (pin "7") (pinfunction "NC_7") (pintype "input+no_connect"))
    )
    (net (code "68") (name "unconnected-(U5-NC-Pad13)") (class "Default")
      (node (ref "U5") (pin "13") (pinfunction "NC_13") (pintype "input+no_connect"))
    )
    (net (code "69") (name "unconnected-(U5-NRESET-Pad9)") (class "Default")
      (node (ref "U5") (pin "9") (pinfunction "NRESET_9") (pintype "input"))
    )
    (net (code "70") (name "unconnected-(U5-ON{slash}OFF-Pad5)") (class "Default")
      (node (ref "U5") (pin "5") (pinfunction "ON/OFF_5") (pintype "input+no_connect"))
    )
    (net (code "71") (name "unconnected-(U5-RXD-Pad3)") (class "Default")
      (node (ref "U5") (pin "3") (pinfunction "RXD_3") (pintype "input+no_connect"))
    )
    (net (code "72") (name "unconnected-(U5-Reserved-Pad15)") (class "Default")
      (node (ref "U5") (pin "15") (pinfunction "Reserved_15") (pintype "input+no_connect"))
    )
    (net (code "73") (name "unconnected-(U5-Reserved-Pad18)") (class "Default")
      (node (ref "U5") (pin "18") (pinfunction "Reserved_18") (pintype "input+no_connect"))
    )
    (net (code "74") (name "unconnected-(U5-SCL-Pad17)") (class "Default")
      (node (ref "U5") (pin "17") (pinfunction "SCL_17") (pintype "input+no_connect"))
    )
    (net (code "75") (name "unconnected-(U5-SDA-Pad16)") (class "Default")
      (node (ref "U5") (pin "16") (pinfunction "SDA_16") (pintype "input+no_connect"))
    )
    (net (code "76") (name "unconnected-(U5-VBAT-Pad6)") (class "Default")
      (node (ref "U5") (pin "6") (pinfunction "VBAT_6") (pintype "input+no_connect"))
    )
    (net (code "77") (name "unconnected-(U5-VCC_RF-Pad14)") (class "Default")
      (node (ref "U5") (pin "14") (pinfunction "VCC_RF_14") (pintype "input+no_connect"))
    )
    (net (code "78") (name "unconnected-(U19-Vin-Pad3)") (class "Default")
      (node (ref "U19") (pin "3") (pinfunction "Vin_3") (pintype "unspecified"))
    )
  )
)
